# RoverWing-V3.net
KiCad netlist of a schematic drawn in EAGLE
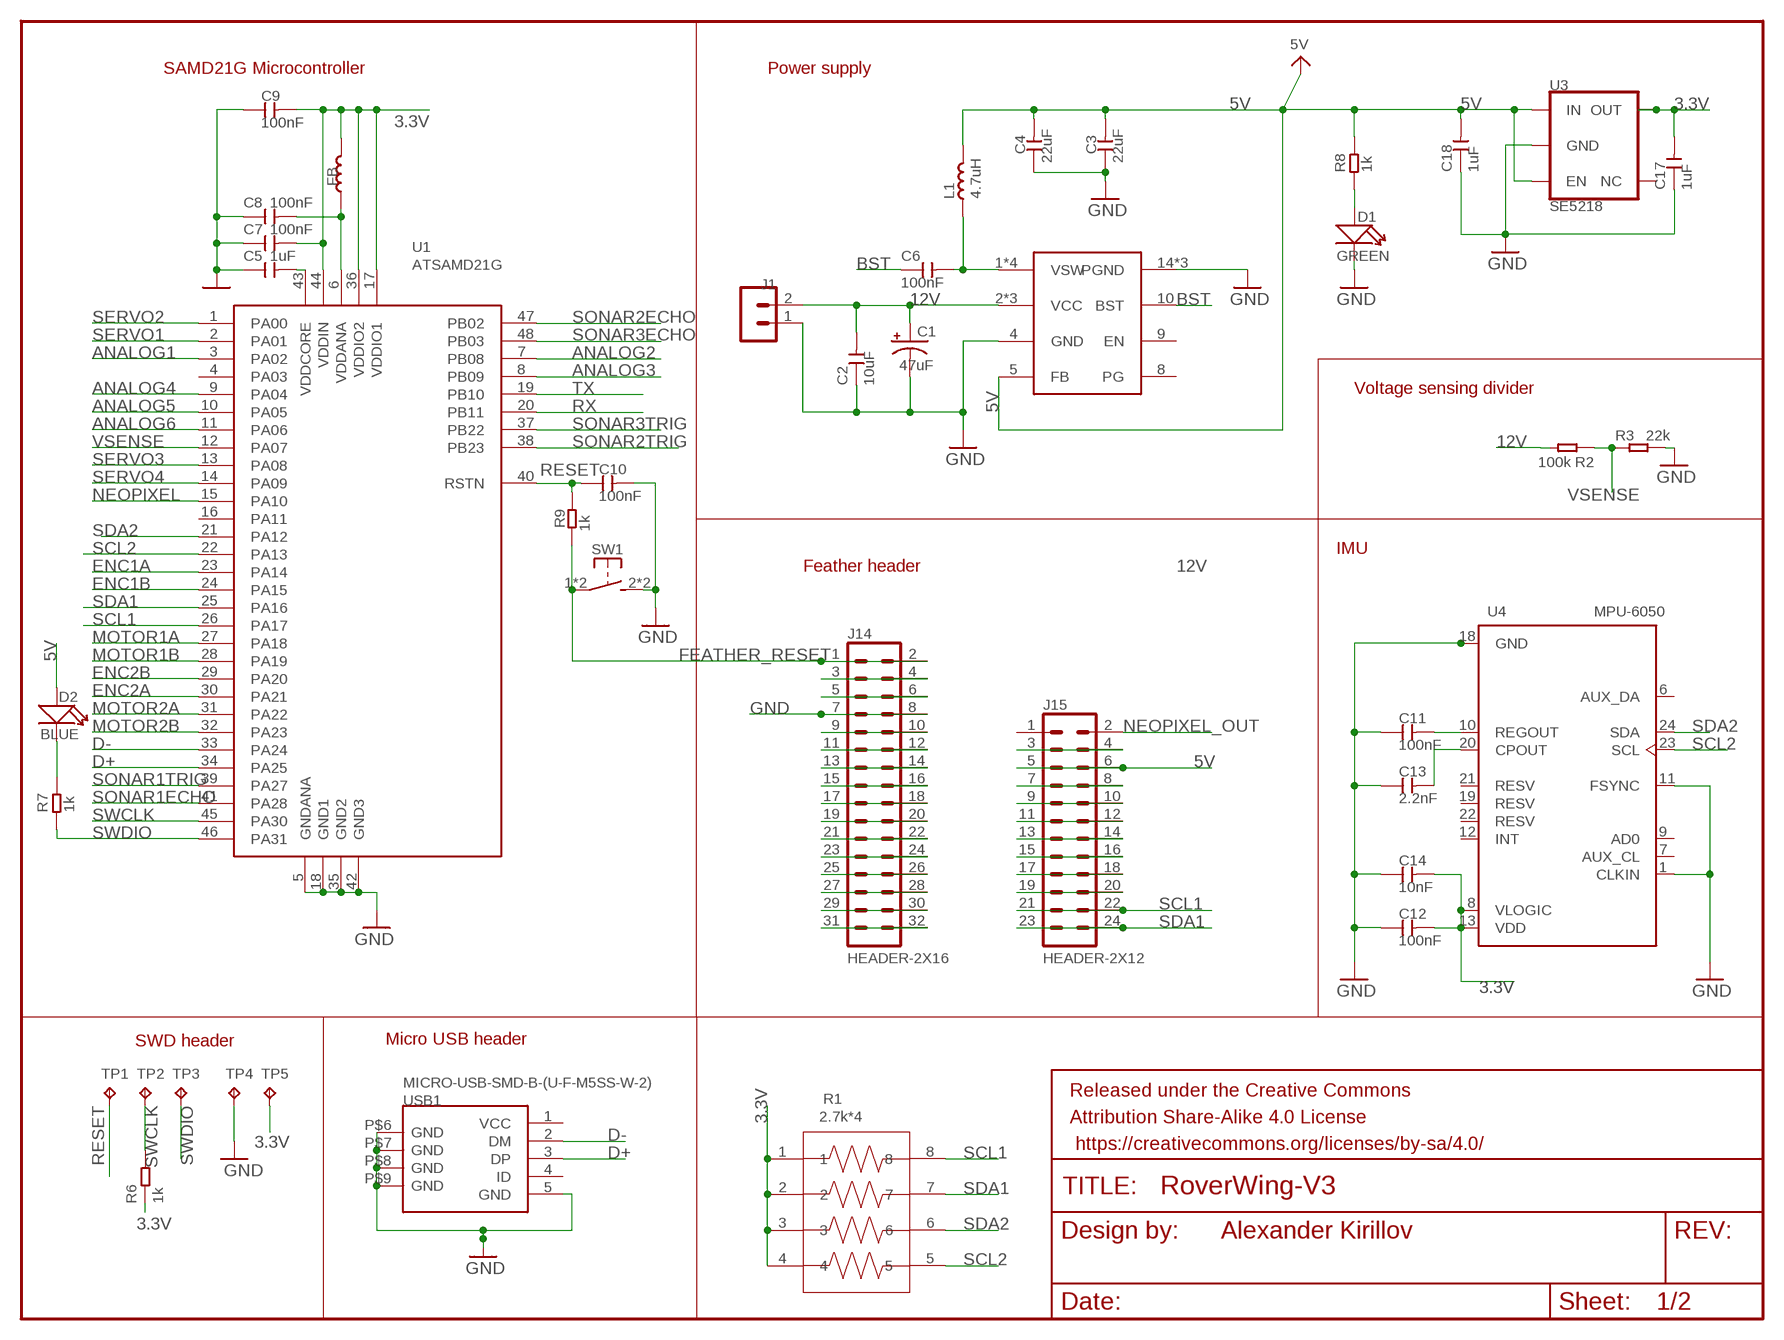
[diagram p0: schematic, sheet 1]
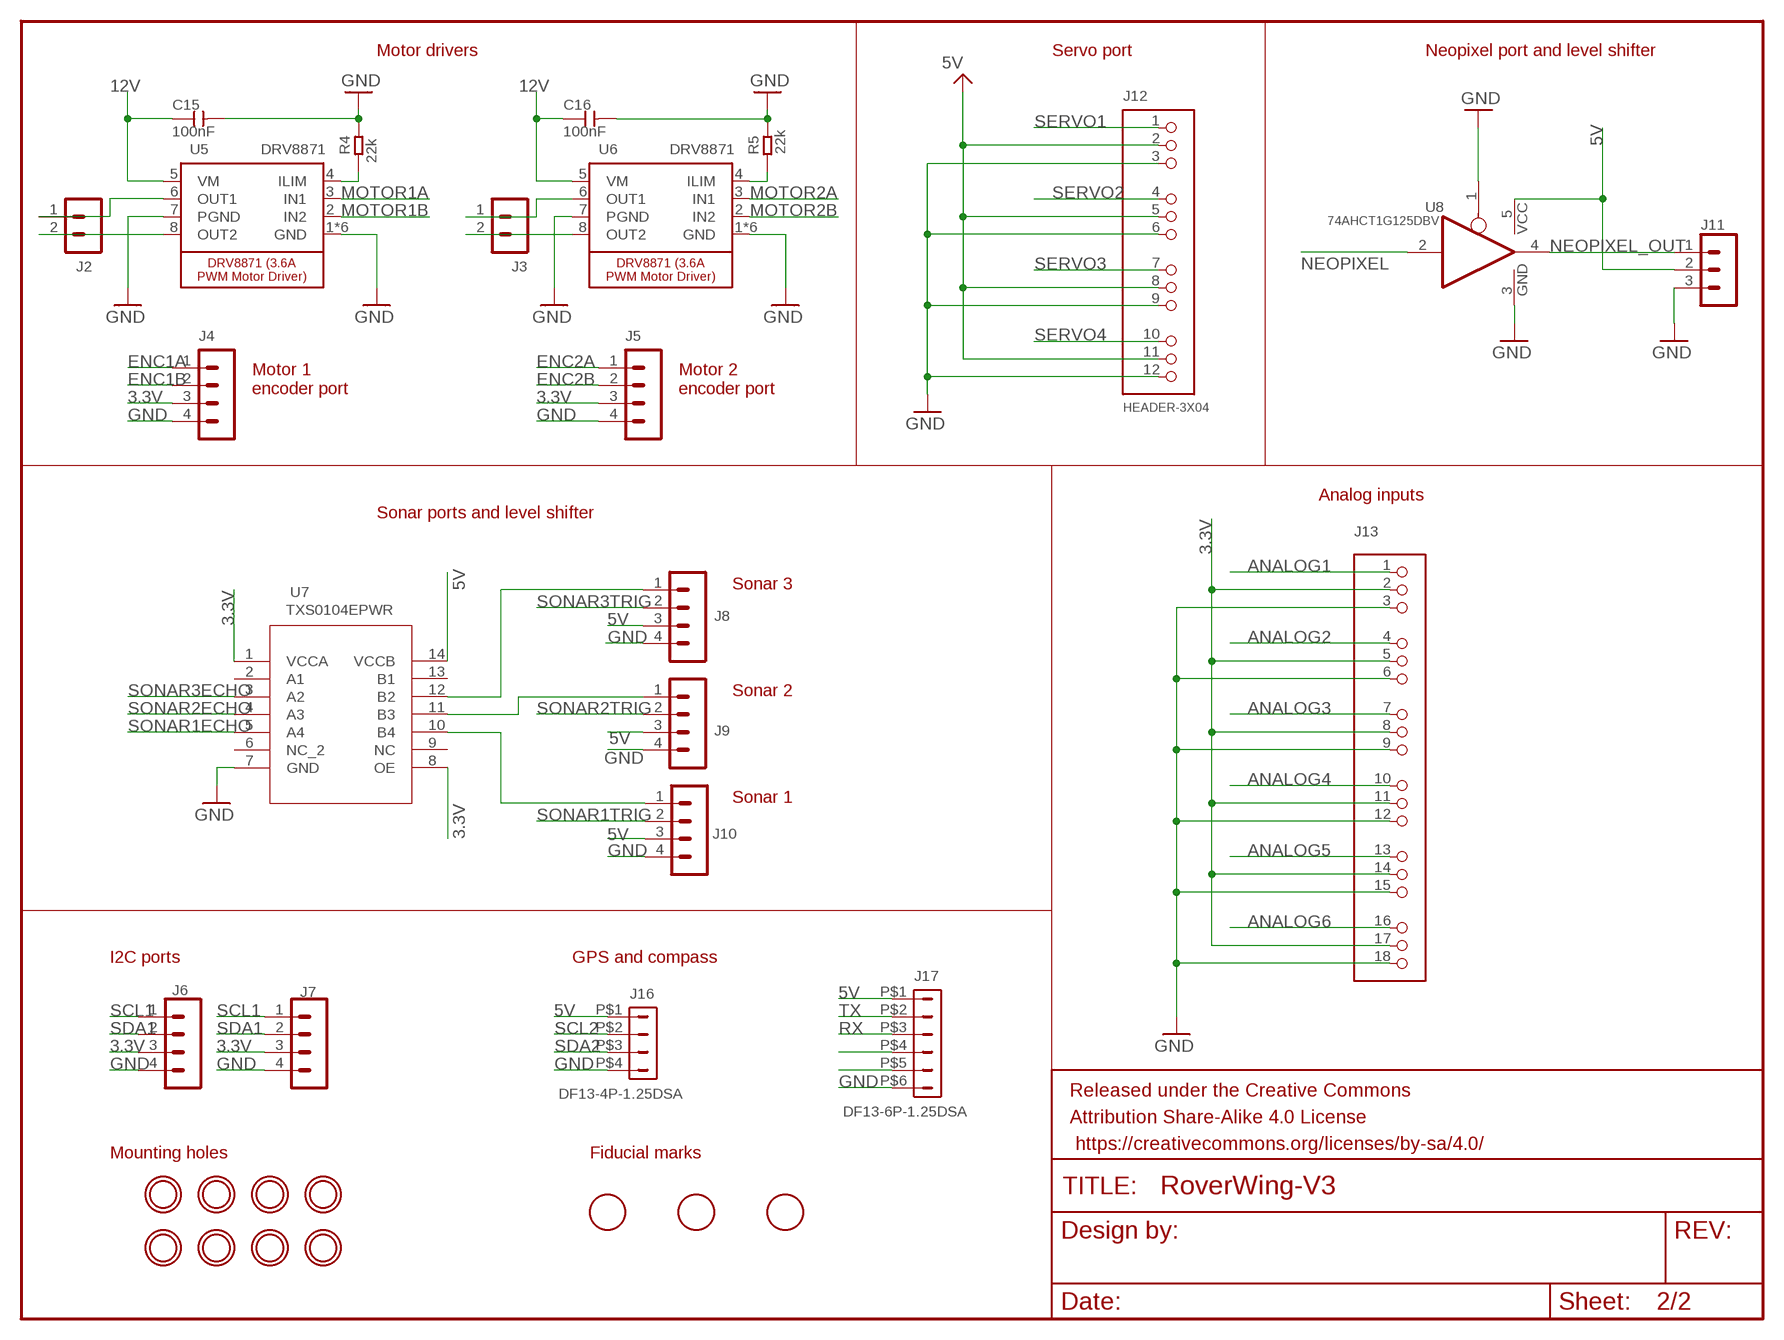
[diagram p1: schematic, sheet 2]

(export (version "E")
  (design (tool "Eeschema 10.0.6"))
  (components
    (comp (ref "C15")
      (value "100nF")
      (footprint "eagle-import:0805")
      (libsource (lib "eagle-import") (part "CAP-CERAMIC-SMD0805"))
    )
    (comp (ref "C16")
      (value "100nF")
      (footprint "eagle-import:0805")
      (libsource (lib "eagle-import") (part "CAP-CERAMIC-SMD0805"))
    )
    (comp (ref "FRAME1")
      (value "FRAME-LETTERNO_PACKAGE")
      (footprint "eagle-import:DUMMY")
      (libsource (lib "eagle-import") (part "FRAME-LETTERNO_PACKAGE"))
    )
    (comp (ref "J2")
      (value "HEADER-VH")
      (footprint "eagle-import:B2P-VH")
      (fields (field (name "PARTNO") "B2P-VH(LF)(SN)  "))
      (libsource (lib "eagle-import") (part "HEADER-VH"))
    )
    (comp (ref "J3")
      (value "HEADER-VH")
      (footprint "eagle-import:B2P-VH")
      (fields (field (name "PARTNO") "B2P-VH(LF)(SN)  "))
      (libsource (lib "eagle-import") (part "HEADER-VH"))
    )
    (comp (ref "J4")
      (value "HEADER-PH-4P")
      (footprint "eagle-import:B4B-PH-K")
      (fields (field (name "PARTNO") "B4B-PH-K-S(LF)(SN)"))
      (libsource (lib "eagle-import") (part "HEADER-PH-4P"))
    )
    (comp (ref "J5")
      (value "HEADER-PH-4P")
      (footprint "eagle-import:B4B-PH-K")
      (fields (field (name "PARTNO") "B4B-PH-K-S(LF)(SN)"))
      (libsource (lib "eagle-import") (part "HEADER-PH-4P"))
    )
    (comp (ref "J6")
      (value "HEADER-PH-4P")
      (footprint "eagle-import:B4B-PH-K")
      (fields (field (name "PARTNO") "B4B-PH-K-S(LF)(SN)"))
      (libsource (lib "eagle-import") (part "HEADER-PH-4P"))
    )
    (comp (ref "J7")
      (value "HEADER-PH-4P")
      (footprint "eagle-import:B4B-PH-K")
      (fields (field (name "PARTNO") "B4B-PH-K-S(LF)(SN)"))
      (libsource (lib "eagle-import") (part "HEADER-PH-4P"))
    )
    (comp (ref "J8")
      (value "HEADER-PH-4P")
      (footprint "eagle-import:B4B-PH-K")
      (fields (field (name "PARTNO") "B4B-PH-K-S(LF)(SN)"))
      (libsource (lib "eagle-import") (part "HEADER-PH-4P"))
    )
    (comp (ref "J9")
      (value "HEADER-PH-4P")
      (footprint "eagle-import:B4B-PH-K")
      (fields (field (name "PARTNO") "B4B-PH-K-S(LF)(SN)"))
      (libsource (lib "eagle-import") (part "HEADER-PH-4P"))
    )
    (comp (ref "J10")
      (value "HEADER-PH-4P")
      (footprint "eagle-import:B4B-PH-K")
      (fields (field (name "PARTNO") "B4B-PH-K-S(LF)(SN)"))
      (libsource (lib "eagle-import") (part "HEADER-PH-4P"))
    )
    (comp (ref "J11")
      (value "HEADER-PH-3P")
      (footprint "eagle-import:B3B-PH-K")
      (fields (field (name "PARTNO") "B3B-PH-K-S(LF)(SN)"))
      (libsource (lib "eagle-import") (part "HEADER-PH-3P"))
    )
    (comp (ref "J12")
      (value "HEADER-3X04")
      (footprint "eagle-import:3X04")
      (libsource (lib "eagle-import") (part "HEADER-3X04"))
    )
    (comp (ref "J13")
      (value "HEADER-3X06\"")
      (footprint "eagle-import:3X06")
      (libsource (lib "eagle-import") (part "HEADER-3X06{dblquote}"))
    )
    (comp (ref "J16")
      (value "DF13-4P-1.25DSA")
      (footprint "eagle-import:DF13-4P-1.25DSA")
      (libsource (lib "eagle-import") (part "DF13-4P-1.25DSA"))
    )
    (comp (ref "J17")
      (value "DF13-6P-1.25DSA")
      (footprint "eagle-import:DF13-6P-1.25DSA")
      (libsource (lib "eagle-import") (part "DF13-6P-1.25DSA"))
    )
    (comp (ref "R4")
      (value "22k")
      (footprint "eagle-import:0805")
      (libsource (lib "eagle-import") (part "RES-SMD-0805"))
    )
    (comp (ref "R5")
      (value "22k")
      (footprint "eagle-import:0805")
      (libsource (lib "eagle-import") (part "RES-SMD-0805"))
    )
    (comp (ref "U$3")
      (value "MOUNTINGHOLE3.0_NPH")
      (footprint "eagle-import:MOUNTINGHOLE_3.0_NPH")
      (libsource (lib "eagle-import") (part "MOUNTINGHOLE3.0_NPH"))
    )
    (comp (ref "U$4")
      (value "MOUNTINGHOLE3.0_NPH")
      (footprint "eagle-import:MOUNTINGHOLE_3.0_NPH")
      (libsource (lib "eagle-import") (part "MOUNTINGHOLE3.0_NPH"))
    )
    (comp (ref "U$11")
      (value "FIDUCIAL")
      (footprint "eagle-import:FIDUCIAL_1MM")
      (libsource (lib "eagle-import") (part "FIDUCIAL"))
    )
    (comp (ref "U$13")
      (value "FIDUCIAL")
      (footprint "eagle-import:FIDUCIAL_1MM")
      (libsource (lib "eagle-import") (part "FIDUCIAL"))
    )
    (comp (ref "U$14")
      (value "MOUNTINGHOLE3.0_NPH")
      (footprint "eagle-import:MOUNTINGHOLE_3.0_NPH")
      (libsource (lib "eagle-import") (part "MOUNTINGHOLE3.0_NPH"))
    )
    (comp (ref "U$15")
      (value "MOUNTINGHOLE3.0_NPH")
      (footprint "eagle-import:MOUNTINGHOLE_3.0_NPH")
      (libsource (lib "eagle-import") (part "MOUNTINGHOLE3.0_NPH"))
    )
    (comp (ref "U$17")
      (value "FIDUCIAL")
      (footprint "eagle-import:FIDUCIAL_1MM")
      (libsource (lib "eagle-import") (part "FIDUCIAL"))
    )
    (comp (ref "U$24")
      (value "MOUNTINGHOLE3.0_NPH")
      (footprint "eagle-import:MOUNTINGHOLE_3.0_NPH")
      (libsource (lib "eagle-import") (part "MOUNTINGHOLE3.0_NPH"))
    )
    (comp (ref "U$25")
      (value "MOUNTINGHOLE3.0_NPH")
      (footprint "eagle-import:MOUNTINGHOLE_3.0_NPH")
      (libsource (lib "eagle-import") (part "MOUNTINGHOLE3.0_NPH"))
    )
    (comp (ref "U$26")
      (value "MOUNTINGHOLE3.0_NPH")
      (footprint "eagle-import:MOUNTINGHOLE_3.0_NPH")
      (libsource (lib "eagle-import") (part "MOUNTINGHOLE3.0_NPH"))
    )
    (comp (ref "U$27")
      (value "MOUNTINGHOLE3.0_NPH")
      (footprint "eagle-import:MOUNTINGHOLE_3.0_NPH")
      (libsource (lib "eagle-import") (part "MOUNTINGHOLE3.0_NPH"))
    )
    (comp (ref "U5")
      (value "DRV8871")
      (footprint "eagle-import:HSOP8")
      (fields (field (name "MANUFACTURER") "TEXAS INSTRUMENTS") (field (name "PARTNO") "DRV8871DDAR"))
      (libsource (lib "eagle-import") (part "DRV8871"))
    )
    (comp (ref "U6")
      (value "DRV8871")
      (footprint "eagle-import:HSOP8")
      (fields (field (name "MANUFACTURER") "TEXAS INSTRUMENTS") (field (name "PARTNO") "DRV8871DDAR"))
      (libsource (lib "eagle-import") (part "DRV8871"))
    )
    (comp (ref "U7")
      (value "TXS0104EPWR")
      (footprint "eagle-import:PW14")
      (fields (field (name "MANUFACTURER") "Texas Instruments"))
      (libsource (lib "eagle-import") (part "TXS0104EPWR"))
    )
    (comp (ref "U8")
      (value "74AHCT1G125DBV")
      (footprint "eagle-import:SOT23-5")
      (fields (field (name "PARTNO") "SN74AHCT1G125DBVR"))
      (libsource (lib "eagle-import") (part "741G125DBVAHCT"))
    )
    (comp (ref "C1")
      (value "47uF")
      (footprint "eagle-import:CAP-6.3X5.4")
      (fields (field (name "PARTNO") "CS1E470M-CRE54 "))
      (libsource (lib "eagle-import") (part "CAP-POL-SMD-6.3X5.4"))
    )
    (comp (ref "C2")
      (value "10uF")
      (footprint "eagle-import:0805")
      (libsource (lib "eagle-import") (part "CAP-CERAMIC-SMD0805"))
    )
    (comp (ref "C3")
      (value "22uF")
      (footprint "eagle-import:0805")
      (libsource (lib "eagle-import") (part "CAP-CERAMIC-SMD0805"))
    )
    (comp (ref "C4")
      (value "22uF")
      (footprint "eagle-import:0805")
      (libsource (lib "eagle-import") (part "CAP-CERAMIC-SMD0805"))
    )
    (comp (ref "C5")
      (value "1uF")
      (footprint "eagle-import:0805")
      (libsource (lib "eagle-import") (part "CAP-CERAMIC-SMD0805"))
    )
    (comp (ref "C6")
      (value "100nF")
      (footprint "eagle-import:0805")
      (libsource (lib "eagle-import") (part "CAP-CERAMIC-SMD0805"))
    )
    (comp (ref "C7")
      (value "100nF")
      (footprint "eagle-import:0805")
      (libsource (lib "eagle-import") (part "CAP-CERAMIC-SMD0805"))
    )
    (comp (ref "C8")
      (value "100nF")
      (footprint "eagle-import:0805")
      (libsource (lib "eagle-import") (part "CAP-CERAMIC-SMD0805"))
    )
    (comp (ref "C9")
      (value "100nF")
      (footprint "eagle-import:0805")
      (libsource (lib "eagle-import") (part "CAP-CERAMIC-SMD0805"))
    )
    (comp (ref "C10")
      (value "100nF")
      (footprint "eagle-import:0805")
      (libsource (lib "eagle-import") (part "CAP-CERAMIC-SMD0805"))
    )
    (comp (ref "C11")
      (value "100nF")
      (footprint "eagle-import:0805")
      (libsource (lib "eagle-import") (part "CAP-CERAMIC-SMD0805"))
    )
    (comp (ref "C12")
      (value "100nF")
      (footprint "eagle-import:0805")
      (libsource (lib "eagle-import") (part "CAP-CERAMIC-SMD0805"))
    )
    (comp (ref "C13")
      (value "2.2nF")
      (footprint "eagle-import:0805")
      (libsource (lib "eagle-import") (part "CAP-CERAMIC-SMD0805"))
    )
    (comp (ref "C14")
      (value "10nF")
      (footprint "eagle-import:0805")
      (libsource (lib "eagle-import") (part "CAP-CERAMIC-SMD0805"))
    )
    (comp (ref "C17")
      (value "1uF")
      (footprint "eagle-import:0805")
      (libsource (lib "eagle-import") (part "CAP-CERAMIC-SMD0805"))
    )
    (comp (ref "C18")
      (value "1uF")
      (footprint "eagle-import:0805")
      (libsource (lib "eagle-import") (part "CAP-CERAMIC-SMD0805"))
    )
    (comp (ref "D1")
      (value "GREEN")
      (footprint "eagle-import:LED-0805")
      (libsource (lib "eagle-import") (part "SMD-LED-0805"))
    )
    (comp (ref "D2")
      (value "BLUE")
      (footprint "eagle-import:LED-0805")
      (libsource (lib "eagle-import") (part "SMD-LED-0805"))
    )
    (comp (ref "FB")
      (value "330R-1500MA")
      (footprint "eagle-import:0805")
      (fields (field (name "PARTNO") "BLM21PG331SN1D"))
      (libsource (lib "eagle-import") (part "SMD-FERRITE-BEAD-330R-1500MA(0805)"))
    )
    (comp (ref "FRAME2")
      (value "FRAME-LETTERNO_PACKAGE")
      (footprint "eagle-import:DUMMY")
      (libsource (lib "eagle-import") (part "FRAME-LETTERNO_PACKAGE"))
    )
    (comp (ref "J1")
      (value "HEADER-VH")
      (footprint "eagle-import:B2P-VH")
      (fields (field (name "PARTNO") "B2P-VH(LF)(SN)  "))
      (libsource (lib "eagle-import") (part "HEADER-VH"))
    )
    (comp (ref "J14")
      (value "HEADER-2X16")
      (footprint "eagle-import:2X16")
      (libsource (lib "eagle-import") (part "HEADER-2X16"))
    )
    (comp (ref "J15")
      (value "HEADER-2X12")
      (footprint "eagle-import:2X12")
      (libsource (lib "eagle-import") (part "HEADER-2X12"))
    )
    (comp (ref "L1")
      (value "4.7uH")
      (footprint "eagle-import:IND_TAIYO_NR6028")
      (fields (field (name "MANUFACTURER") "TAIYO YUDEN") (field (name "PARTNO") "NR6028T4R7M"))
      (libsource (lib "eagle-import") (part "NR6028T4R7M"))
    )
    (comp (ref "R1")
      (value "2.7k*4")
      (footprint "eagle-import:0603_4")
      (fields (field (name "PARTNO") "RTA03-4D272JTP "))
      (libsource (lib "eagle-import") (part "RES_ARRAY-2.7KX40603X4"))
    )
    (comp (ref "R2")
      (value "100k")
      (footprint "eagle-import:0805")
      (libsource (lib "eagle-import") (part "RES-SMD-0805"))
    )
    (comp (ref "R3")
      (value "22k")
      (footprint "eagle-import:0805")
      (libsource (lib "eagle-import") (part "RES-SMD-0805"))
    )
    (comp (ref "R6")
      (value "1k")
      (footprint "eagle-import:0805")
      (libsource (lib "eagle-import") (part "RES-SMD-0805"))
    )
    (comp (ref "R7")
      (value "1k")
      (footprint "eagle-import:0805")
      (libsource (lib "eagle-import") (part "RES-SMD-0805"))
    )
    (comp (ref "R8")
      (value "1k")
      (footprint "eagle-import:0805")
      (libsource (lib "eagle-import") (part "RES-SMD-0805"))
    )
    (comp (ref "R9")
      (value "1k")
      (footprint "eagle-import:0805")
      (libsource (lib "eagle-import") (part "RES-SMD-0805"))
    )
    (comp (ref "SW1")
      (value "SW-TACTILE-4.5X4.5_SMD")
      (footprint "eagle-import:TL3305")
      (libsource (lib "eagle-import") (part "SW-TACTILE-4.5X4.5_SMD"))
    )
    (comp (ref "TP1")
      (value "TPTP15R")
      (footprint "eagle-import:TP15R")
      (libsource (lib "eagle-import") (part "TPTP15R"))
    )
    (comp (ref "TP2")
      (value "TPTP15R")
      (footprint "eagle-import:TP15R")
      (libsource (lib "eagle-import") (part "TPTP15R"))
    )
    (comp (ref "TP3")
      (value "TPTP15R")
      (footprint "eagle-import:TP15R")
      (libsource (lib "eagle-import") (part "TPTP15R"))
    )
    (comp (ref "TP4")
      (value "TPTP15R")
      (footprint "eagle-import:TP15R")
      (libsource (lib "eagle-import") (part "TPTP15R"))
    )
    (comp (ref "TP5")
      (value "TPTP15R")
      (footprint "eagle-import:TP15R")
      (libsource (lib "eagle-import") (part "TPTP15R"))
    )
    (comp (ref "U1")
      (value "ATSAMD21G")
      (footprint "eagle-import:TQFP-48-EDITED")
      (fields (field (name "MANUFACTURER") "Microchip Technology") (field (name "PARTNO") "ATSAMD21G18A-AU"))
      (libsource (lib "eagle-import") (part "ATSAMD21G"))
    )
    (comp (ref "U2")
      (value "TS30013-M050QFNR")
      (footprint "eagle-import:QFN16-3X3MM")
      (libsource (lib "eagle-import") (part "TS30013-MQFNR050"))
    )
    (comp (ref "U3")
      (value "SE5218")
      (footprint "eagle-import:SOT23-5")
      (fields (field (name "PARTNO") "SE5218ALG-LF "))
      (libsource (lib "eagle-import") (part "SE5218"))
    )
    (comp (ref "U4")
      (value "MPU-6050")
      (footprint "eagle-import:QFN50P400X400X95-24N")
      (fields (field (name "MANUFACTURER") "TDK InvenSense"))
      (libsource (lib "eagle-import") (part "MPU-6050"))
    )
    (comp (ref "USB1")
      (value "MICRO-USB-SMD-B-(U-F-M5SS-W-2)")
      (footprint "eagle-import:MICRO-USB-NO-TABS")
      (fields (field (name "PARTNO") "U-F-M5SS-W-2 "))
      (libsource (lib "eagle-import") (part "MICRO-USB-SMD-B-(U-F-M5SS-W-2)"))
    )
  )
  (nets
    (net (code "1") (name "3.3V") (class "Default")
      (node (ref "C12") (pin "2") (pinfunction "2_2") (pintype "passive"))
      (node (ref "C14") (pin "2") (pinfunction "2_2") (pintype "passive"))
      (node (ref "C17") (pin "2") (pinfunction "2_2") (pintype "passive"))
      (node (ref "C7") (pin "2") (pinfunction "2_2") (pintype "passive"))
      (node (ref "C9") (pin "2") (pinfunction "2_2") (pintype "passive"))
      (node (ref "FB") (pin "2") (pinfunction "2_2") (pintype "passive"))
      (node (ref "J13") (pin "11") (pinfunction "11_11") (pintype "passive"))
      (node (ref "J13") (pin "14") (pinfunction "14_14") (pintype "passive"))
      (node (ref "J13") (pin "17") (pinfunction "17_17") (pintype "passive"))
      (node (ref "J13") (pin "2") (pinfunction "2_2") (pintype "passive"))
      (node (ref "J13") (pin "5") (pinfunction "5_5") (pintype "passive"))
      (node (ref "J13") (pin "8") (pinfunction "8_8") (pintype "passive"))
      (node (ref "J4") (pin "3") (pinfunction "3_3") (pintype "passive"))
      (node (ref "J5") (pin "3") (pinfunction "3_3") (pintype "passive"))
      (node (ref "J6") (pin "3") (pinfunction "3_3") (pintype "passive"))
      (node (ref "J7") (pin "3") (pinfunction "3_3") (pintype "passive"))
      (node (ref "R1") (pin "1") (pinfunction "1_1") (pintype "passive"))
      (node (ref "R1") (pin "2") (pinfunction "2_2") (pintype "passive"))
      (node (ref "R1") (pin "3") (pinfunction "3_3") (pintype "passive"))
      (node (ref "R1") (pin "4") (pinfunction "4_4") (pintype "passive"))
      (node (ref "R6") (pin "1") (pinfunction "1_1") (pintype "passive"))
      (node (ref "TP5") (pin "TP") (pinfunction "TP_TP") (pintype "input"))
      (node (ref "U1") (pin "17") (pinfunction "VDDIO1_17") (pintype "power_in"))
      (node (ref "U1") (pin "36") (pinfunction "VDDIO2_36") (pintype "power_in"))
      (node (ref "U1") (pin "44") (pinfunction "VDDIN_44") (pintype "power_in"))
      (node (ref "U3") (pin "5") (pinfunction "OUT_5") (pintype "output"))
      (node (ref "U4") (pin "13") (pinfunction "VDD_13") (pintype "power_in"))
      (node (ref "U4") (pin "8") (pinfunction "VLOGIC_8") (pintype "power_in"))
      (node (ref "U7") (pin "1") (pinfunction "VCCA_1") (pintype "power_in"))
      (node (ref "U7") (pin "8") (pinfunction "OE_8") (pintype "output"))
    )
    (net (code "2") (name "5V") (class "Default")
      (node (ref "C18") (pin "2") (pinfunction "2_2") (pintype "passive"))
      (node (ref "C3") (pin "2") (pinfunction "2_2") (pintype "passive"))
      (node (ref "C4") (pin "2") (pinfunction "2_2") (pintype "passive"))
      (node (ref "D2") (pin "+") (pinfunction "+_+") (pintype "passive"))
      (node (ref "J10") (pin "3") (pinfunction "3_3") (pintype "passive"))
      (node (ref "J11") (pin "2") (pinfunction "2_2") (pintype "passive"))
      (node (ref "J12") (pin "11") (pinfunction "11_11") (pintype "passive"))
      (node (ref "J12") (pin "2") (pinfunction "2_2") (pintype "passive"))
      (node (ref "J12") (pin "5") (pinfunction "5_5") (pintype "passive"))
      (node (ref "J12") (pin "8") (pinfunction "8_8") (pintype "passive"))
      (node (ref "J15") (pin "5") (pinfunction "5_5") (pintype "passive"))
      (node (ref "J15") (pin "6") (pinfunction "6_6") (pintype "passive"))
      (node (ref "J16") (pin "P$1") (pinfunction "1_P$1") (pintype "passive"))
      (node (ref "J17") (pin "P$1") (pinfunction "1_P$1") (pintype "passive"))
      (node (ref "J8") (pin "3") (pinfunction "3_3") (pintype "passive"))
      (node (ref "J9") (pin "3") (pinfunction "3_3") (pintype "passive"))
      (node (ref "L1") (pin "2") (pinfunction "2_2") (pintype "passive"))
      (node (ref "R8") (pin "2") (pinfunction "2_2") (pintype "passive"))
      (node (ref "U2") (pin "5") (pinfunction "FB_5") (pintype "bidirectional"))
      (node (ref "U3") (pin "1") (pinfunction "IN_1") (pintype "input"))
      (node (ref "U3") (pin "3") (pinfunction "EN_3") (pintype "input"))
      (node (ref "U7") (pin "14") (pinfunction "VCCB_14") (pintype "power_in"))
      (node (ref "U8") (pin "5") (pinfunction "VCC_5") (pintype "power_in"))
    )
    (net (code "3") (name "12V") (class "Default")
      (node (ref "C1") (pin "+") (pinfunction "+_+") (pintype "passive"))
      (node (ref "C15") (pin "1") (pinfunction "1_1") (pintype "passive"))
      (node (ref "C16") (pin "1") (pinfunction "1_1") (pintype "passive"))
      (node (ref "C2") (pin "2") (pinfunction "2_2") (pintype "passive"))
      (node (ref "J1") (pin "2") (pinfunction "2_2") (pintype "passive"))
      (node (ref "R2") (pin "2") (pinfunction "2_2") (pintype "passive"))
      (node (ref "U2") (pin "11") (pinfunction "VCC_11") (pintype "power_in"))
      (node (ref "U2") (pin "2") (pinfunction "VCC_2") (pintype "power_in"))
      (node (ref "U2") (pin "3") (pinfunction "VCC_3") (pintype "power_in"))
      (node (ref "U5") (pin "5") (pinfunction "VM_5") (pintype "power_in"))
      (node (ref "U6") (pin "5") (pinfunction "VM_5") (pintype "power_in"))
    )
    (net (code "4") (name "ANALOG1") (class "Default")
      (node (ref "J13") (pin "1") (pinfunction "1_1") (pintype "passive"))
      (node (ref "U1") (pin "3") (pinfunction "PA02_3") (pintype "bidirectional"))
    )
    (net (code "5") (name "ANALOG2") (class "Default")
      (node (ref "J13") (pin "4") (pinfunction "4_4") (pintype "passive"))
      (node (ref "U1") (pin "7") (pinfunction "PB08_7") (pintype "bidirectional"))
    )
    (net (code "6") (name "ANALOG3") (class "Default")
      (node (ref "J13") (pin "7") (pinfunction "7_7") (pintype "passive"))
      (node (ref "U1") (pin "8") (pinfunction "PB09_8") (pintype "bidirectional"))
    )
    (net (code "7") (name "ANALOG4") (class "Default")
      (node (ref "J13") (pin "10") (pinfunction "10_10") (pintype "passive"))
      (node (ref "U1") (pin "9") (pinfunction "PA04_9") (pintype "bidirectional"))
    )
    (net (code "8") (name "ANALOG5") (class "Default")
      (node (ref "J13") (pin "13") (pinfunction "13_13") (pintype "passive"))
      (node (ref "U1") (pin "10") (pinfunction "PA05_10") (pintype "bidirectional"))
    )
    (net (code "9") (name "ANALOG6") (class "Default")
      (node (ref "J13") (pin "16") (pinfunction "16_16") (pintype "passive"))
      (node (ref "U1") (pin "11") (pinfunction "PA06_11") (pintype "bidirectional"))
    )
    (net (code "10") (name "BST") (class "Default")
      (node (ref "C6") (pin "1") (pinfunction "1_1") (pintype "passive"))
      (node (ref "U2") (pin "10") (pinfunction "BST_10") (pintype "bidirectional"))
    )
    (net (code "11") (name "D+") (class "Default")
      (node (ref "U1") (pin "34") (pinfunction "PA25_34") (pintype "bidirectional"))
      (node (ref "USB1") (pin "3") (pinfunction "DP_3") (pintype "bidirectional"))
    )
    (net (code "12") (name "D-") (class "Default")
      (node (ref "U1") (pin "33") (pinfunction "PA24_33") (pintype "bidirectional"))
      (node (ref "USB1") (pin "2") (pinfunction "DM_2") (pintype "bidirectional"))
    )
    (net (code "13") (name "ENC1A") (class "Default")
      (node (ref "J4") (pin "1") (pinfunction "1_1") (pintype "passive"))
      (node (ref "U1") (pin "23") (pinfunction "PA14_23") (pintype "bidirectional"))
    )
    (net (code "14") (name "ENC1B") (class "Default")
      (node (ref "J4") (pin "2") (pinfunction "2_2") (pintype "passive"))
      (node (ref "U1") (pin "24") (pinfunction "PA15_24") (pintype "bidirectional"))
    )
    (net (code "15") (name "ENC2A") (class "Default")
      (node (ref "J5") (pin "1") (pinfunction "1_1") (pintype "passive"))
      (node (ref "U1") (pin "30") (pinfunction "PA21_30") (pintype "bidirectional"))
    )
    (net (code "16") (name "ENC2B") (class "Default")
      (node (ref "J5") (pin "2") (pinfunction "2_2") (pintype "passive"))
      (node (ref "U1") (pin "29") (pinfunction "PA20_29") (pintype "bidirectional"))
    )
    (net (code "17") (name "FEATHER_RESET") (class "Default")
      (node (ref "J14") (pin "1") (pinfunction "1_1") (pintype "passive"))
      (node (ref "J14") (pin "2") (pinfunction "2_2") (pintype "passive"))
      (node (ref "R9") (pin "1") (pinfunction "1_1") (pintype "passive"))
      (node (ref "SW1") (pin "1") (pinfunction "P1_1") (pintype "passive"))
      (node (ref "SW1") (pin "4") (pinfunction "P1_4") (pintype "passive"))
    )
    (net (code "18") (name "GND") (class "Default")
      (node (ref "C1") (pin "-") (pinfunction "-_-") (pintype "passive"))
      (node (ref "C10") (pin "2") (pinfunction "2_2") (pintype "passive"))
      (node (ref "C11") (pin "1") (pinfunction "1_1") (pintype "passive"))
      (node (ref "C12") (pin "1") (pinfunction "1_1") (pintype "passive"))
      (node (ref "C13") (pin "1") (pinfunction "1_1") (pintype "passive"))
      (node (ref "C14") (pin "1") (pinfunction "1_1") (pintype "passive"))
      (node (ref "C15") (pin "2") (pinfunction "2_2") (pintype "passive"))
      (node (ref "C16") (pin "2") (pinfunction "2_2") (pintype "passive"))
      (node (ref "C17") (pin "1") (pinfunction "1_1") (pintype "passive"))
      (node (ref "C18") (pin "1") (pinfunction "1_1") (pintype "passive"))
      (node (ref "C2") (pin "1") (pinfunction "1_1") (pintype "passive"))
      (node (ref "C3") (pin "1") (pinfunction "1_1") (pintype "passive"))
      (node (ref "C4") (pin "1") (pinfunction "1_1") (pintype "passive"))
      (node (ref "C5") (pin "1") (pinfunction "1_1") (pintype "passive"))
      (node (ref "C7") (pin "1") (pinfunction "1_1") (pintype "passive"))
      (node (ref "C8") (pin "1") (pinfunction "1_1") (pintype "passive"))
      (node (ref "C9") (pin "1") (pinfunction "1_1") (pintype "passive"))
      (node (ref "D1") (pin "-") (pinfunction "-_-") (pintype "passive"))
      (node (ref "J1") (pin "1") (pinfunction "1_1") (pintype "passive"))
      (node (ref "J10") (pin "4") (pinfunction "4_4") (pintype "passive"))
      (node (ref "J11") (pin "3") (pinfunction "3_3") (pintype "passive"))
      (node (ref "J12") (pin "12") (pinfunction "12_12") (pintype "passive"))
      (node (ref "J12") (pin "3") (pinfunction "3_3") (pintype "passive"))
      (node (ref "J12") (pin "6") (pinfunction "6_6") (pintype "passive"))
      (node (ref "J12") (pin "9") (pinfunction "9_9") (pintype "passive"))
      (node (ref "J13") (pin "12") (pinfunction "12_12") (pintype "passive"))
      (node (ref "J13") (pin "15") (pinfunction "15_15") (pintype "passive"))
      (node (ref "J13") (pin "18") (pinfunction "18_18") (pintype "passive"))
      (node (ref "J13") (pin "3") (pinfunction "3_3") (pintype "passive"))
      (node (ref "J13") (pin "6") (pinfunction "6_6") (pintype "passive"))
      (node (ref "J13") (pin "9") (pinfunction "9_9") (pintype "passive"))
      (node (ref "J14") (pin "7") (pinfunction "7_7") (pintype "passive"))
      (node (ref "J14") (pin "8") (pinfunction "8_8") (pintype "passive"))
      (node (ref "J16") (pin "P$4") (pinfunction "4_P$4") (pintype "passive"))
      (node (ref "J17") (pin "P$6") (pinfunction "6_P$6") (pintype "passive"))
      (node (ref "J4") (pin "4") (pinfunction "4_4") (pintype "passive"))
      (node (ref "J5") (pin "4") (pinfunction "4_4") (pintype "passive"))
      (node (ref "J6") (pin "4") (pinfunction "4_4") (pintype "passive"))
      (node (ref "J7") (pin "4") (pinfunction "4_4") (pintype "passive"))
      (node (ref "J8") (pin "4") (pinfunction "4_4") (pintype "passive"))
      (node (ref "J9") (pin "4") (pinfunction "4_4") (pintype "passive"))
      (node (ref "R3") (pin "2") (pinfunction "2_2") (pintype "passive"))
      (node (ref "R4") (pin "2") (pinfunction "2_2") (pintype "passive"))
      (node (ref "R5") (pin "2") (pinfunction "2_2") (pintype "passive"))
      (node (ref "SW1") (pin "2") (pinfunction "S1_2") (pintype "passive"))
      (node (ref "SW1") (pin "3") (pinfunction "S1_3") (pintype "passive"))
      (node (ref "TP4") (pin "TP") (pinfunction "TP_TP") (pintype "input"))
      (node (ref "U1") (pin "18") (pinfunction "GND1_18") (pintype "power_in"))
      (node (ref "U1") (pin "35") (pinfunction "GND2_35") (pintype "power_in"))
      (node (ref "U1") (pin "42") (pinfunction "GND3_42") (pintype "power_in"))
      (node (ref "U1") (pin "5") (pinfunction "GNDANA_5") (pintype "power_in"))
      (node (ref "U2") (pin "14") (pinfunction "PGND_14") (pintype "power_in"))
      (node (ref "U2") (pin "15") (pinfunction "PGND_15") (pintype "power_in"))
      (node (ref "U2") (pin "4") (pinfunction "GND_4") (pintype "power_in"))
      (node (ref "U2") (pin "EXT") (pinfunction "PGND_EXT") (pintype "power_in"))
      (node (ref "U3") (pin "2") (pinfunction "GND_2") (pintype "power_in"))
      (node (ref "U4") (pin "1") (pinfunction "CLKIN_1") (pintype "input"))
      (node (ref "U4") (pin "11") (pinfunction "FSYNC_11") (pintype "input"))
      (node (ref "U4") (pin "18") (pinfunction "GND_18") (pintype "power_in"))
      (node (ref "U5") (pin "1") (pinfunction "GND_1") (pintype "power_in"))
      (node (ref "U5") (pin "7") (pinfunction "PGND_7") (pintype "power_in"))
      (node (ref "U5") (pin "GND") (pinfunction "GND_GND") (pintype "power_in"))
      (node (ref "U5") (pin "P$1") (pinfunction "GND_P$1") (pintype "power_in"))
      (node (ref "U5") (pin "P$2") (pinfunction "GND_P$2") (pintype "power_in"))
      (node (ref "U5") (pin "P$3") (pinfunction "GND_P$3") (pintype "power_in"))
      (node (ref "U5") (pin "P$4") (pinfunction "GND_P$4") (pintype "power_in"))
      (node (ref "U6") (pin "1") (pinfunction "GND_1") (pintype "power_in"))
      (node (ref "U6") (pin "7") (pinfunction "PGND_7") (pintype "power_in"))
      (node (ref "U6") (pin "GND") (pinfunction "GND_GND") (pintype "power_in"))
      (node (ref "U6") (pin "P$1") (pinfunction "GND_P$1") (pintype "power_in"))
      (node (ref "U6") (pin "P$2") (pinfunction "GND_P$2") (pintype "power_in"))
      (node (ref "U6") (pin "P$3") (pinfunction "GND_P$3") (pintype "power_in"))
      (node (ref "U6") (pin "P$4") (pinfunction "GND_P$4") (pintype "power_in"))
      (node (ref "U7") (pin "7") (pinfunction "GND_7") (pintype "power_in"))
      (node (ref "U8") (pin "1") (pinfunction "OE_1") (pintype "input"))
      (node (ref "U8") (pin "3") (pinfunction "GND_3") (pintype "power_in"))
      (node (ref "USB1") (pin "5") (pinfunction "GND_5") (pintype "bidirectional"))
      (node (ref "USB1") (pin "P$6") (pinfunction "GND_P$6") (pintype "bidirectional"))
      (node (ref "USB1") (pin "P$7") (pinfunction "GND_P$7") (pintype "bidirectional"))
      (node (ref "USB1") (pin "P$8") (pinfunction "GND_P$8") (pintype "bidirectional"))
      (node (ref "USB1") (pin "P$9") (pinfunction "GND_P$9") (pintype "bidirectional"))
    )
    (net (code "19") (name "MOTOR1A") (class "Default")
      (node (ref "U1") (pin "27") (pinfunction "PA18_27") (pintype "bidirectional"))
      (node (ref "U5") (pin "3") (pinfunction "IN1_3") (pintype "input"))
    )
    (net (code "20") (name "MOTOR1B") (class "Default")
      (node (ref "U1") (pin "28") (pinfunction "PA19_28") (pintype "bidirectional"))
      (node (ref "U5") (pin "2") (pinfunction "IN2_2") (pintype "input"))
    )
    (net (code "21") (name "MOTOR2A") (class "Default")
      (node (ref "U1") (pin "31") (pinfunction "PA22_31") (pintype "bidirectional"))
      (node (ref "U6") (pin "3") (pinfunction "IN1_3") (pintype "input"))
    )
    (net (code "22") (name "MOTOR2B") (class "Default")
      (node (ref "U1") (pin "32") (pinfunction "PA23_32") (pintype "bidirectional"))
      (node (ref "U6") (pin "2") (pinfunction "IN2_2") (pintype "input"))
    )
    (net (code "23") (name "NEOPIXEL") (class "Default")
      (node (ref "U1") (pin "15") (pinfunction "PA10_15") (pintype "bidirectional"))
      (node (ref "U8") (pin "2") (pinfunction "I_2") (pintype "input"))
    )
    (net (code "24") (name "NEOPIXEL_OUT") (class "Default")
      (node (ref "J11") (pin "1") (pinfunction "1_1") (pintype "passive"))
      (node (ref "J15") (pin "2") (pinfunction "2_2") (pintype "passive"))
      (node (ref "U8") (pin "4") (pinfunction "O_4") (pintype "tri_state"))
    )
    (net (code "25") (name "Net-(C6-Pad2)") (class "Default")
      (node (ref "C6") (pin "2") (pinfunction "2_2") (pintype "passive"))
      (node (ref "L1") (pin "1") (pinfunction "1_1") (pintype "passive"))
      (node (ref "U2") (pin "1") (pinfunction "VSW_1") (pintype "bidirectional"))
      (node (ref "U2") (pin "12") (pinfunction "VSW_12") (pintype "bidirectional"))
      (node (ref "U2") (pin "13") (pinfunction "VSW_13") (pintype "bidirectional"))
      (node (ref "U2") (pin "16") (pinfunction "VSW_16") (pintype "bidirectional"))
    )
    (net (code "26") (name "Net-(D1-Pad+)") (class "Default")
      (node (ref "D1") (pin "+") (pinfunction "+_+") (pintype "passive"))
      (node (ref "R8") (pin "1") (pinfunction "1_1") (pintype "passive"))
    )
    (net (code "27") (name "Net-(D2-Pad-)") (class "Default")
      (node (ref "D2") (pin "-") (pinfunction "-_-") (pintype "passive"))
      (node (ref "R7") (pin "2") (pinfunction "2_2") (pintype "passive"))
    )
    (net (code "28") (name "Net-(J14-Pad3)") (class "Default")
      (node (ref "J14") (pin "3") (pinfunction "3_3") (pintype "passive"))
      (node (ref "J14") (pin "4") (pinfunction "4_4") (pintype "passive"))
    )
    (net (code "29") (name "Net-(J14-Pad5)") (class "Default")
      (node (ref "J14") (pin "5") (pinfunction "5_5") (pintype "passive"))
      (node (ref "J14") (pin "6") (pinfunction "6_6") (pintype "passive"))
    )
    (net (code "30") (name "Net-(J14-Pad10)") (class "Default")
      (node (ref "J14") (pin "10") (pinfunction "10_10") (pintype "passive"))
      (node (ref "J14") (pin "9") (pinfunction "9_9") (pintype "passive"))
    )
    (net (code "31") (name "Net-(J14-Pad11)") (class "Default")
      (node (ref "J14") (pin "11") (pinfunction "11_11") (pintype "passive"))
      (node (ref "J14") (pin "12") (pinfunction "12_12") (pintype "passive"))
    )
    (net (code "32") (name "Net-(J14-Pad13)") (class "Default")
      (node (ref "J14") (pin "13") (pinfunction "13_13") (pintype "passive"))
      (node (ref "J14") (pin "14") (pinfunction "14_14") (pintype "passive"))
    )
    (net (code "33") (name "Net-(J14-Pad15)") (class "Default")
      (node (ref "J14") (pin "15") (pinfunction "15_15") (pintype "passive"))
      (node (ref "J14") (pin "16") (pinfunction "16_16") (pintype "passive"))
    )
    (net (code "34") (name "Net-(J14-Pad17)") (class "Default")
      (node (ref "J14") (pin "17") (pinfunction "17_17") (pintype "passive"))
      (node (ref "J14") (pin "18") (pinfunction "18_18") (pintype "passive"))
    )
    (net (code "35") (name "Net-(J14-Pad19)") (class "Default")
      (node (ref "J14") (pin "19") (pinfunction "19_19") (pintype "passive"))
      (node (ref "J14") (pin "20") (pinfunction "20_20") (pintype "passive"))
    )
    (net (code "36") (name "Net-(J14-Pad21)") (class "Default")
      (node (ref "J14") (pin "21") (pinfunction "21_21") (pintype "passive"))
      (node (ref "J14") (pin "22") (pinfunction "22_22") (pintype "passive"))
    )
    (net (code "37") (name "Net-(J14-Pad23)") (class "Default")
      (node (ref "J14") (pin "23") (pinfunction "23_23") (pintype "passive"))
      (node (ref "J14") (pin "24") (pinfunction "24_24") (pintype "passive"))
    )
    (net (code "38") (name "Net-(J14-Pad25)") (class "Default")
      (node (ref "J14") (pin "25") (pinfunction "25_25") (pintype "passive"))
      (node (ref "J14") (pin "26") (pinfunction "26_26") (pintype "passive"))
    )
    (net (code "39") (name "Net-(J14-Pad27)") (class "Default")
      (node (ref "J14") (pin "27") (pinfunction "27_27") (pintype "passive"))
      (node (ref "J14") (pin "28") (pinfunction "28_28") (pintype "passive"))
    )
    (net (code "40") (name "Net-(J14-Pad29)") (class "Default")
      (node (ref "J14") (pin "29") (pinfunction "29_29") (pintype "passive"))
      (node (ref "J14") (pin "30") (pinfunction "30_30") (pintype "passive"))
    )
    (net (code "41") (name "Net-(J14-Pad31)") (class "Default")
      (node (ref "J14") (pin "31") (pinfunction "31_31") (pintype "passive"))
      (node (ref "J14") (pin "32") (pinfunction "32_32") (pintype "passive"))
    )
    (net (code "42") (name "Net-(J15-Pad3)") (class "Default")
      (node (ref "J15") (pin "3") (pinfunction "3_3") (pintype "passive"))
      (node (ref "J15") (pin "4") (pinfunction "4_4") (pintype "passive"))
    )
    (net (code "43") (name "Net-(J15-Pad7)") (class "Default")
      (node (ref "J15") (pin "7") (pinfunction "7_7") (pintype "passive"))
      (node (ref "J15") (pin "8") (pinfunction "8_8") (pintype "passive"))
    )
    (net (code "44") (name "Net-(J15-Pad10)") (class "Default")
      (node (ref "J15") (pin "10") (pinfunction "10_10") (pintype "passive"))
      (node (ref "J15") (pin "9") (pinfunction "9_9") (pintype "passive"))
    )
    (net (code "45") (name "Net-(J15-Pad11)") (class "Default")
      (node (ref "J15") (pin "11") (pinfunction "11_11") (pintype "passive"))
      (node (ref "J15") (pin "12") (pinfunction "12_12") (pintype "passive"))
    )
    (net (code "46") (name "Net-(J15-Pad13)") (class "Default")
      (node (ref "J15") (pin "13") (pinfunction "13_13") (pintype "passive"))
      (node (ref "J15") (pin "14") (pinfunction "14_14") (pintype "passive"))
    )
    (net (code "47") (name "Net-(J15-Pad15)") (class "Default")
      (node (ref "J15") (pin "15") (pinfunction "15_15") (pintype "passive"))
      (node (ref "J15") (pin "16") (pinfunction "16_16") (pintype "passive"))
    )
    (net (code "48") (name "Net-(J15-Pad17)") (class "Default")
      (node (ref "J15") (pin "17") (pinfunction "17_17") (pintype "passive"))
      (node (ref "J15") (pin "18") (pinfunction "18_18") (pintype "passive"))
    )
    (net (code "49") (name "Net-(J15-Pad19)") (class "Default")
      (node (ref "J15") (pin "19") (pinfunction "19_19") (pintype "passive"))
      (node (ref "J15") (pin "20") (pinfunction "20_20") (pintype "passive"))
    )
    (net (code "50") (name "Net-(U1-VDDANA)") (class "Default")
      (node (ref "C8") (pin "2") (pinfunction "2_2") (pintype "passive"))
      (node (ref "FB") (pin "1") (pinfunction "1_1") (pintype "passive"))
      (node (ref "U1") (pin "6") (pinfunction "VDDANA_6") (pintype "power_in"))
    )
    (net (code "51") (name "Net-(U1-VDDCORE)") (class "Default")
      (node (ref "C5") (pin "2") (pinfunction "2_2") (pintype "passive"))
      (node (ref "U1") (pin "43") (pinfunction "VDDCORE_43") (pintype "power_in"))
    )
    (net (code "52") (name "Net-(U4-CPOUT)") (class "Default")
      (node (ref "C13") (pin "2") (pinfunction "2_2") (pintype "passive"))
      (node (ref "U4") (pin "20") (pinfunction "CPOUT_20") (pintype "passive"))
    )
    (net (code "53") (name "Net-(U4-REGOUT)") (class "Default")
      (node (ref "C11") (pin "2") (pinfunction "2_2") (pintype "passive"))
      (node (ref "U4") (pin "10") (pinfunction "REGOUT_10") (pintype "passive"))
    )
    (net (code "54") (name "Net-(U5-ILIM)") (class "Default")
      (node (ref "R4") (pin "1") (pinfunction "1_1") (pintype "passive"))
      (node (ref "U5") (pin "4") (pinfunction "ILIM_4") (pintype "input"))
    )
    (net (code "55") (name "Net-(U5-OUT1)") (class "Default")
      (node (ref "J2") (pin "1") (pinfunction "1_1") (pintype "passive"))
      (node (ref "U5") (pin "6") (pinfunction "OUT1_6") (pintype "output"))
    )
    (net (code "56") (name "Net-(U5-OUT2)") (class "Default")
      (node (ref "J2") (pin "2") (pinfunction "2_2") (pintype "passive"))
      (node (ref "U5") (pin "8") (pinfunction "OUT2_8") (pintype "output"))
    )
    (net (code "57") (name "Net-(U6-ILIM)") (class "Default")
      (node (ref "R5") (pin "1") (pinfunction "1_1") (pintype "passive"))
      (node (ref "U6") (pin "4") (pinfunction "ILIM_4") (pintype "input"))
    )
    (net (code "58") (name "Net-(U6-OUT1)") (class "Default")
      (node (ref "J3") (pin "1") (pinfunction "1_1") (pintype "passive"))
      (node (ref "U6") (pin "6") (pinfunction "OUT1_6") (pintype "output"))
    )
    (net (code "59") (name "Net-(U6-OUT2)") (class "Default")
      (node (ref "J3") (pin "2") (pinfunction "2_2") (pintype "passive"))
      (node (ref "U6") (pin "8") (pinfunction "OUT2_8") (pintype "output"))
    )
    (net (code "60") (name "Net-(U7-B2)") (class "Default")
      (node (ref "J8") (pin "1") (pinfunction "1_1") (pintype "passive"))
      (node (ref "U7") (pin "12") (pinfunction "B2_12") (pintype "bidirectional"))
    )
    (net (code "61") (name "Net-(U7-B3)") (class "Default")
      (node (ref "J9") (pin "1") (pinfunction "1_1") (pintype "passive"))
      (node (ref "U7") (pin "11") (pinfunction "B3_11") (pintype "bidirectional"))
    )
    (net (code "62") (name "Net-(U7-B4)") (class "Default")
      (node (ref "J10") (pin "1") (pinfunction "1_1") (pintype "passive"))
      (node (ref "U7") (pin "10") (pinfunction "B4_10") (pintype "bidirectional"))
    )
    (net (code "63") (name "RESET") (class "Default")
      (node (ref "C10") (pin "1") (pinfunction "1_1") (pintype "passive"))
      (node (ref "R9") (pin "2") (pinfunction "2_2") (pintype "passive"))
      (node (ref "TP1") (pin "TP") (pinfunction "TP_TP") (pintype "input"))
      (node (ref "U1") (pin "40") (pinfunction "RSTN_40") (pintype "bidirectional"))
    )
    (net (code "64") (name "RX") (class "Default")
      (node (ref "J17") (pin "P$3") (pinfunction "3_P$3") (pintype "passive"))
      (node (ref "U1") (pin "20") (pinfunction "PB11_20") (pintype "bidirectional"))
    )
    (net (code "65") (name "SCL1") (class "Default")
      (node (ref "J15") (pin "21") (pinfunction "21_21") (pintype "passive"))
      (node (ref "J15") (pin "22") (pinfunction "22_22") (pintype "passive"))
      (node (ref "J6") (pin "1") (pinfunction "1_1") (pintype "passive"))
      (node (ref "J7") (pin "1") (pinfunction "1_1") (pintype "passive"))
      (node (ref "R1") (pin "8") (pinfunction "8_8") (pintype "passive"))
      (node (ref "U1") (pin "26") (pinfunction "PA17_26") (pintype "bidirectional"))
    )
    (net (code "66") (name "SCL2") (class "Default")
      (node (ref "J16") (pin "P$2") (pinfunction "2_P$2") (pintype "passive"))
      (node (ref "R1") (pin "5") (pinfunction "5_5") (pintype "passive"))
      (node (ref "U1") (pin "22") (pinfunction "PA13_22") (pintype "bidirectional"))
      (node (ref "U4") (pin "23") (pinfunction "SCL_23") (pintype "input"))
    )
    (net (code "67") (name "SDA1") (class "Default")
      (node (ref "J15") (pin "23") (pinfunction "23_23") (pintype "passive"))
      (node (ref "J15") (pin "24") (pinfunction "24_24") (pintype "passive"))
      (node (ref "J6") (pin "2") (pinfunction "2_2") (pintype "passive"))
      (node (ref "J7") (pin "2") (pinfunction "2_2") (pintype "passive"))
      (node (ref "R1") (pin "7") (pinfunction "7_7") (pintype "passive"))
      (node (ref "U1") (pin "25") (pinfunction "PA16_25") (pintype "bidirectional"))
    )
    (net (code "68") (name "SDA2") (class "Default")
      (node (ref "J16") (pin "P$3") (pinfunction "3_P$3") (pintype "passive"))
      (node (ref "R1") (pin "6") (pinfunction "6_6") (pintype "passive"))
      (node (ref "U1") (pin "21") (pinfunction "PA12_21") (pintype "bidirectional"))
      (node (ref "U4") (pin "24") (pinfunction "SDA_24") (pintype "bidirectional"))
    )
    (net (code "69") (name "SERVO1") (class "Default")
      (node (ref "J12") (pin "1") (pinfunction "1_1") (pintype "passive"))
      (node (ref "U1") (pin "2") (pinfunction "PA01_2") (pintype "bidirectional"))
    )
    (net (code "70") (name "SERVO2") (class "Default")
      (node (ref "J12") (pin "4") (pinfunction "4_4") (pintype "passive"))
      (node (ref "U1") (pin "1") (pinfunction "PA00_1") (pintype "bidirectional"))
    )
    (net (code "71") (name "SERVO3") (class "Default")
      (node (ref "J12") (pin "7") (pinfunction "7_7") (pintype "passive"))
      (node (ref "U1") (pin "13") (pinfunction "PA08_13") (pintype "bidirectional"))
    )
    (net (code "72") (name "SERVO4") (class "Default")
      (node (ref "J12") (pin "10") (pinfunction "10_10") (pintype "passive"))
      (node (ref "U1") (pin "14") (pinfunction "PA09_14") (pintype "bidirectional"))
    )
    (net (code "73") (name "SONAR1ECHO") (class "Default")
      (node (ref "U1") (pin "41") (pinfunction "PA28_41") (pintype "bidirectional"))
      (node (ref "U7") (pin "5") (pinfunction "A4_5") (pintype "bidirectional"))
    )
    (net (code "74") (name "SONAR1TRIG") (class "Default")
      (node (ref "J10") (pin "2") (pinfunction "2_2") (pintype "passive"))
      (node (ref "U1") (pin "39") (pinfunction "PA27_39") (pintype "bidirectional"))
    )
    (net (code "75") (name "SONAR2ECHO") (class "Default")
      (node (ref "U1") (pin "47") (pinfunction "PB02_47") (pintype "bidirectional"))
      (node (ref "U7") (pin "4") (pinfunction "A3_4") (pintype "bidirectional"))
    )
    (net (code "76") (name "SONAR2TRIG") (class "Default")
      (node (ref "J9") (pin "2") (pinfunction "2_2") (pintype "passive"))
      (node (ref "U1") (pin "38") (pinfunction "PB23_38") (pintype "bidirectional"))
    )
    (net (code "77") (name "SONAR3ECHO") (class "Default")
      (node (ref "U1") (pin "48") (pinfunction "PB03_48") (pintype "bidirectional"))
      (node (ref "U7") (pin "3") (pinfunction "A2_3") (pintype "bidirectional"))
    )
    (net (code "78") (name "SONAR3TRIG") (class "Default")
      (node (ref "J8") (pin "2") (pinfunction "2_2") (pintype "passive"))
      (node (ref "U1") (pin "37") (pinfunction "PB22_37") (pintype "bidirectional"))
    )
    (net (code "79") (name "SWCLK") (class "Default")
      (node (ref "R6") (pin "2") (pinfunction "2_2") (pintype "passive"))
      (node (ref "TP2") (pin "TP") (pinfunction "TP_TP") (pintype "input"))
      (node (ref "U1") (pin "45") (pinfunction "PA30_45") (pintype "bidirectional"))
    )
    (net (code "80") (name "SWDIO") (class "Default")
      (node (ref "R7") (pin "1") (pinfunction "1_1") (pintype "passive"))
      (node (ref "TP3") (pin "TP") (pinfunction "TP_TP") (pintype "input"))
      (node (ref "U1") (pin "46") (pinfunction "PA31_46") (pintype "bidirectional"))
    )
    (net (code "81") (name "TX") (class "Default")
      (node (ref "J17") (pin "P$2") (pinfunction "2_P$2") (pintype "passive"))
      (node (ref "U1") (pin "19") (pinfunction "PB10_19") (pintype "bidirectional"))
    )
    (net (code "82") (name "VSENSE") (class "Default")
      (node (ref "R2") (pin "1") (pinfunction "1_1") (pintype "passive"))
      (node (ref "R3") (pin "1") (pinfunction "1_1") (pintype "passive"))
      (node (ref "U1") (pin "12") (pinfunction "PA07_12") (pintype "bidirectional"))
    )
    (net (code "83") (name "unconnected-(J15-Pad1)") (class "Default")
      (node (ref "J15") (pin "1") (pinfunction "1_1") (pintype "passive"))
    )
    (net (code "84") (name "unconnected-(J17-4-PadP$4)") (class "Default")
      (node (ref "J17") (pin "P$4") (pinfunction "4_P$4") (pintype "passive"))
    )
    (net (code "85") (name "unconnected-(J17-5-PadP$5)") (class "Default")
      (node (ref "J17") (pin "P$5") (pinfunction "5_P$5") (pintype "passive"))
    )
    (net (code "86") (name "unconnected-(U1-PA03-Pad4)") (class "Default")
      (node (ref "U1") (pin "4") (pinfunction "PA03_4") (pintype "bidirectional"))
    )
    (net (code "87") (name "unconnected-(U1-PA11-Pad16)") (class "Default")
      (node (ref "U1") (pin "16") (pinfunction "PA11_16") (pintype "bidirectional"))
    )
    (net (code "88") (name "unconnected-(U2-EN-Pad9)") (class "Default")
      (node (ref "U2") (pin "9") (pinfunction "EN_9") (pintype "bidirectional"))
    )
    (net (code "89") (name "unconnected-(U2-PG-Pad8)") (class "Default")
      (node (ref "U2") (pin "8") (pinfunction "PG_8") (pintype "bidirectional"))
    )
    (net (code "90") (name "unconnected-(U3-NC-Pad4)") (class "Default")
      (node (ref "U3") (pin "4") (pinfunction "NC_4") (pintype "no_connect"))
    )
    (net (code "91") (name "unconnected-(U4-AD0-Pad9)") (class "Default")
      (node (ref "U4") (pin "9") (pinfunction "AD0_9") (pintype "input"))
    )
    (net (code "92") (name "unconnected-(U4-AUX_CL-Pad7)") (class "Default")
      (node (ref "U4") (pin "7") (pinfunction "AUX_CL_7") (pintype "input"))
    )
    (net (code "93") (name "unconnected-(U4-AUX_DA-Pad6)") (class "Default")
      (node (ref "U4") (pin "6") (pinfunction "AUX_DA_6") (pintype "bidirectional"))
    )
    (net (code "94") (name "unconnected-(U4-INT-Pad12)") (class "Default")
      (node (ref "U4") (pin "12") (pinfunction "INT_12") (pintype "output"))
    )
    (net (code "95") (name "unconnected-(U4-RESV-Pad19)") (class "Default")
      (node (ref "U4") (pin "19") (pinfunction "RESV_19") (pintype "passive"))
    )
    (net (code "96") (name "unconnected-(U4-RESV-Pad21)") (class "Default")
      (node (ref "U4") (pin "21") (pinfunction "RESV_21") (pintype "passive"))
    )
    (net (code "97") (name "unconnected-(U4-RESV-Pad22)") (class "Default")
      (node (ref "U4") (pin "22") (pinfunction "RESV_22") (pintype "passive"))
    )
    (net (code "98") (name "unconnected-(U7-A1-Pad2)") (class "Default")
      (node (ref "U7") (pin "2") (pinfunction "A1_2") (pintype "bidirectional"))
    )
    (net (code "99") (name "unconnected-(U7-B1-Pad13)") (class "Default")
      (node (ref "U7") (pin "13") (pinfunction "B1_13") (pintype "bidirectional"))
    )
    (net (code "100") (name "unconnected-(U7-NC-Pad9)") (class "Default")
      (node (ref "U7") (pin "9") (pinfunction "NC_9") (pintype "no_connect"))
    )
    (net (code "101") (name "unconnected-(U7-NC_2-Pad6)") (class "Default")
      (node (ref "U7") (pin "6") (pinfunction "NC_2_6") (pintype "no_connect"))
    )
    (net (code "102") (name "unconnected-(USB1-ID-Pad4)") (class "Default")
      (node (ref "USB1") (pin "4") (pinfunction "ID_4") (pintype "bidirectional"))
    )
    (net (code "103") (name "unconnected-(USB1-VCC-Pad1)") (class "Default")
      (node (ref "USB1") (pin "1") (pinfunction "VCC_1") (pintype "bidirectional"))
    )
  )
)
